# 05-MCU_02.net
KiCad netlist of a schematic drawn in Altium Designer
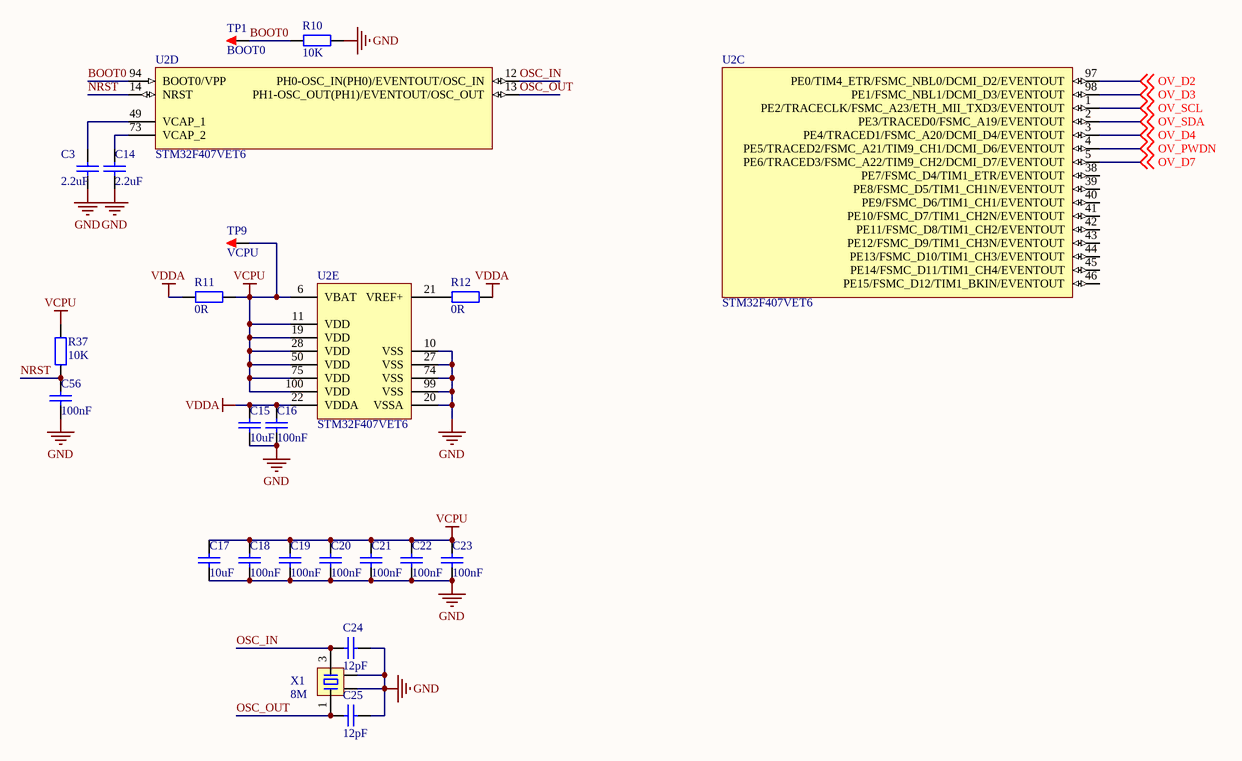
[diagram p0: 05-MCU_02.SchDoc]

(export (version "E")
  (design (tool "Eeschema 10.0.6"))
  (components
    (comp (ref "C3")
      (value "2.2uF")
      (footprint "C0603_M")
      (description "贴片电容/MLCC电容")
      (libsource (lib "0.1 - 电阻-电容-电感-保险丝-晶振-晶体-磁珠-电位器-法拉电容-馈通电容") (part "C"))
    )
    (comp (ref "C14")
      (value "2.2uF")
      (footprint "C0603_M")
      (description "贴片电容/MLCC电容")
      (libsource (lib "0.1 - 电阻-电容-电感-保险丝-晶振-晶体-磁珠-电位器-法拉电容-馈通电容") (part "C"))
    )
    (comp (ref "C15")
      (value "10uF")
      (footprint "C0603_M")
      (description "贴片电容/MLCC电容")
      (libsource (lib "0.1 - 电阻-电容-电感-保险丝-晶振-晶体-磁珠-电位器-法拉电容-馈通电容") (part "C"))
    )
    (comp (ref "C16")
      (value "100nF")
      (footprint "C0603_M")
      (description "贴片电容/MLCC电容")
      (libsource (lib "0.1 - 电阻-电容-电感-保险丝-晶振-晶体-磁珠-电位器-法拉电容-馈通电容") (part "C"))
    )
    (comp (ref "C17")
      (value "10uF")
      (footprint "C0603_M")
      (description "贴片电容/MLCC电容")
      (libsource (lib "0.1 - 电阻-电容-电感-保险丝-晶振-晶体-磁珠-电位器-法拉电容-馈通电容") (part "C"))
    )
    (comp (ref "C18")
      (value "100nF")
      (footprint "C0603_M")
      (description "贴片电容/MLCC电容")
      (libsource (lib "0.1 - 电阻-电容-电感-保险丝-晶振-晶体-磁珠-电位器-法拉电容-馈通电容") (part "C"))
    )
    (comp (ref "C19")
      (value "100nF")
      (footprint "C0603_M")
      (description "贴片电容/MLCC电容")
      (libsource (lib "0.1 - 电阻-电容-电感-保险丝-晶振-晶体-磁珠-电位器-法拉电容-馈通电容") (part "C"))
    )
    (comp (ref "C20")
      (value "100nF")
      (footprint "C0603_M")
      (description "贴片电容/MLCC电容")
      (libsource (lib "0.1 - 电阻-电容-电感-保险丝-晶振-晶体-磁珠-电位器-法拉电容-馈通电容") (part "C"))
    )
    (comp (ref "C21")
      (value "100nF")
      (footprint "C0603_M")
      (description "贴片电容/MLCC电容")
      (libsource (lib "0.1 - 电阻-电容-电感-保险丝-晶振-晶体-磁珠-电位器-法拉电容-馈通电容") (part "C"))
    )
    (comp (ref "C22")
      (value "100nF")
      (footprint "C0603_M")
      (description "贴片电容/MLCC电容")
      (libsource (lib "0.1 - 电阻-电容-电感-保险丝-晶振-晶体-磁珠-电位器-法拉电容-馈通电容") (part "C"))
    )
    (comp (ref "C23")
      (value "100nF")
      (footprint "C0603_M")
      (description "贴片电容/MLCC电容")
      (libsource (lib "0.1 - 电阻-电容-电感-保险丝-晶振-晶体-磁珠-电位器-法拉电容-馈通电容") (part "C"))
    )
    (comp (ref "C24")
      (value "12pF")
      (footprint "C0603_M")
      (description "贴片电容/MLCC电容")
      (libsource (lib "0.1 - 电阻-电容-电感-保险丝-晶振-晶体-磁珠-电位器-法拉电容-馈通电容") (part "C"))
    )
    (comp (ref "C25")
      (value "12pF")
      (footprint "C0603_M")
      (description "贴片电容/MLCC电容")
      (libsource (lib "0.1 - 电阻-电容-电感-保险丝-晶振-晶体-磁珠-电位器-法拉电容-馈通电容") (part "C"))
    )
    (comp (ref "C56")
      (value "100nF")
      (footprint "C0603_M")
      (description "贴片电容/MLCC电容")
      (libsource (lib "0.1 - 电阻-电容-电感-保险丝-晶振-晶体-磁珠-电位器-法拉电容-馈通电容") (part "C"))
    )
    (comp (ref "R10")
      (value "10K")
      (footprint "R0603_M")
      (description "贴片电阻")
      (libsource (lib "0.1 - 电阻-电容-电感-保险丝-晶振-晶体-磁珠-电位器-法拉电容-馈通电容") (part "R"))
    )
    (comp (ref "R11")
      (value "0R")
      (footprint "R0603_M")
      (description "贴片电阻")
      (libsource (lib "0.1 - 电阻-电容-电感-保险丝-晶振-晶体-磁珠-电位器-法拉电容-馈通电容") (part "R"))
    )
    (comp (ref "R12")
      (value "0R")
      (footprint "R0603_M")
      (description "贴片电阻")
      (libsource (lib "0.1 - 电阻-电容-电感-保险丝-晶振-晶体-磁珠-电位器-法拉电容-馈通电容") (part "R"))
    )
    (comp (ref "R37")
      (value "10K")
      (footprint "R0603_M")
      (description "贴片电阻")
      (libsource (lib "0.1 - 电阻-电容-电感-保险丝-晶振-晶体-磁珠-电位器-法拉电容-馈通电容") (part "R"))
    )
    (comp (ref "TP1")
      (value "BOOT0")
      (footprint "TEST 1.6")
      (description "测试点")
      (libsource (lib "0.5 - 按键_开关_蜂鸣器_电池_测试点_Mark点_铜柱") (part "TEST"))
    )
    (comp (ref "TP9")
      (value "VCPU")
      (footprint "TEST 1.6")
      (description "测试点")
      (libsource (lib "0.5 - 按键_开关_蜂鸣器_电池_测试点_Mark点_铜柱") (part "TEST"))
    )
    (comp (ref "U2")
      (value "STM32F407VET6")
      (footprint "LQFP100_V")
      (libsource (lib "STM32 F4") (part "STM32F407VET6"))
    )
    (comp (ref "X1")
      (value "8M")
      (footprint "XTAL-3225-4P")
      (description "4脚无源晶振(谐振器）")
      (libsource (lib "0.1 - 电阻-电容-电感-保险丝-晶振-晶体-磁珠-电位器-法拉电容-馈通电容") (part "XTAL-4P"))
    )
  )
  (nets
    (net (code "1") (name "/BOOT0") (class "Default")
      (node (ref "R10") (pin "2") (pinfunction "2_2") (pintype "passive"))
      (node (ref "TP1") (pin "1") (pinfunction "1_1") (pintype "passive"))
      (node (ref "U2") (pin "94") (pinfunction "BOOT0/VPP_94") (pintype "input"))
    )
    (net (code "2") (name "/NRST") (class "Default")
      (node (ref "C56") (pin "1") (pinfunction "1_1") (pintype "passive"))
      (node (ref "R37") (pin "1") (pinfunction "1_1") (pintype "passive"))
      (node (ref "U2") (pin "14") (pinfunction "NRST_14") (pintype "bidirectional"))
    )
    (net (code "3") (name "/OSC_IN") (class "Default")
      (node (ref "C24") (pin "1") (pinfunction "1_1") (pintype "passive"))
      (node (ref "U2") (pin "12") (pinfunction "PH0-OSC_IN(PH0)/EVENTOUT/OSC_IN_12") (pintype "bidirectional"))
      (node (ref "X1") (pin "3") (pinfunction "3_3") (pintype "passive"))
    )
    (net (code "4") (name "/OSC_OUT") (class "Default")
      (node (ref "C25") (pin "1") (pinfunction "1_1") (pintype "passive"))
      (node (ref "U2") (pin "13") (pinfunction "PH1-OSC_OUT(PH1)/EVENTOUT/OSC_OUT_13") (pintype "bidirectional"))
      (node (ref "X1") (pin "1") (pinfunction "1_1") (pintype "passive"))
    )
    (net (code "5") (name "GND") (class "Default")
      (node (ref "C14") (pin "2") (pinfunction "2_2") (pintype "passive"))
      (node (ref "C15") (pin "2") (pinfunction "2_2") (pintype "passive"))
      (node (ref "C16") (pin "2") (pinfunction "2_2") (pintype "passive"))
      (node (ref "C17") (pin "2") (pinfunction "2_2") (pintype "passive"))
      (node (ref "C18") (pin "2") (pinfunction "2_2") (pintype "passive"))
      (node (ref "C19") (pin "2") (pinfunction "2_2") (pintype "passive"))
      (node (ref "C20") (pin "2") (pinfunction "2_2") (pintype "passive"))
      (node (ref "C21") (pin "2") (pinfunction "2_2") (pintype "passive"))
      (node (ref "C22") (pin "2") (pinfunction "2_2") (pintype "passive"))
      (node (ref "C23") (pin "2") (pinfunction "2_2") (pintype "passive"))
      (node (ref "C24") (pin "2") (pinfunction "2_2") (pintype "passive"))
      (node (ref "C25") (pin "2") (pinfunction "2_2") (pintype "passive"))
      (node (ref "C3") (pin "2") (pinfunction "2_2") (pintype "passive"))
      (node (ref "C56") (pin "2") (pinfunction "2_2") (pintype "passive"))
      (node (ref "R10") (pin "1") (pinfunction "1_1") (pintype "passive"))
      (node (ref "U2") (pin "10") (pinfunction "VSS_10") (pintype "power_in"))
      (node (ref "U2") (pin "20") (pinfunction "VSSA_20") (pintype "power_in"))
      (node (ref "U2") (pin "27") (pinfunction "VSS_27") (pintype "power_in"))
      (node (ref "U2") (pin "74") (pinfunction "VSS_74") (pintype "power_in"))
      (node (ref "U2") (pin "99") (pinfunction "VSS_99") (pintype "power_in"))
      (node (ref "X1") (pin "2") (pinfunction "2_2") (pintype "passive"))
      (node (ref "X1") (pin "4") (pinfunction "4_4") (pintype "passive"))
    )
    (net (code "6") (name "Net-(U2D-VCAP_1)") (class "Default")
      (node (ref "C3") (pin "1") (pinfunction "1_1") (pintype "passive"))
      (node (ref "U2") (pin "49") (pinfunction "VCAP_1_49") (pintype "power_in"))
    )
    (net (code "7") (name "Net-(U2D-VCAP_2)") (class "Default")
      (node (ref "C14") (pin "1") (pinfunction "1_1") (pintype "passive"))
      (node (ref "U2") (pin "73") (pinfunction "VCAP_2_73") (pintype "power_in"))
    )
    (net (code "8") (name "Net-(U2E-VREF+)") (class "Default")
      (node (ref "R12") (pin "2") (pinfunction "2_2") (pintype "passive"))
      (node (ref "U2") (pin "21") (pinfunction "VREF+_21") (pintype "power_in"))
    )
    (net (code "9") (name "OV_D2") (class "Default")
      (node (ref "U2") (pin "97") (pinfunction "PE0/TIM4_ETR/FSMC_NBL0/DCMI_D2/EVENTOUT_97") (pintype "bidirectional"))
    )
    (net (code "10") (name "OV_D3") (class "Default")
      (node (ref "U2") (pin "98") (pinfunction "PE1/FSMC_NBL1/DCMI_D3/EVENTOUT_98") (pintype "bidirectional"))
    )
    (net (code "11") (name "OV_D4") (class "Default")
      (node (ref "U2") (pin "3") (pinfunction "PE4/TRACED1/FSMC_A20/DCMI_D4/EVENTOUT_3") (pintype "bidirectional"))
    )
    (net (code "12") (name "OV_D7") (class "Default")
      (node (ref "U2") (pin "5") (pinfunction "PE6/TRACED3/FSMC_A22/TIM9_CH2/DCMI_D7/EVENTOUT_5") (pintype "bidirectional"))
    )
    (net (code "13") (name "OV_PWDN") (class "Default")
      (node (ref "U2") (pin "4") (pinfunction "PE5/TRACED2/FSMC_A21/TIM9_CH1/DCMI_D6/EVENTOUT_4") (pintype "bidirectional"))
    )
    (net (code "14") (name "OV_SCL") (class "Default")
      (node (ref "U2") (pin "1") (pinfunction "PE2/TRACECLK/FSMC_A23/ETH_MII_TXD3/EVENTOUT_1") (pintype "bidirectional"))
    )
    (net (code "15") (name "OV_SDA") (class "Default")
      (node (ref "U2") (pin "2") (pinfunction "PE3/TRACED0/FSMC_A19/EVENTOUT_2") (pintype "bidirectional"))
    )
    (net (code "16") (name "VCPU") (class "Default")
      (node (ref "C17") (pin "1") (pinfunction "1_1") (pintype "passive"))
      (node (ref "C18") (pin "1") (pinfunction "1_1") (pintype "passive"))
      (node (ref "C19") (pin "1") (pinfunction "1_1") (pintype "passive"))
      (node (ref "C20") (pin "1") (pinfunction "1_1") (pintype "passive"))
      (node (ref "C21") (pin "1") (pinfunction "1_1") (pintype "passive"))
      (node (ref "C22") (pin "1") (pinfunction "1_1") (pintype "passive"))
      (node (ref "C23") (pin "1") (pinfunction "1_1") (pintype "passive"))
      (node (ref "R11") (pin "1") (pinfunction "1_1") (pintype "passive"))
      (node (ref "R37") (pin "2") (pinfunction "2_2") (pintype "passive"))
      (node (ref "TP9") (pin "1") (pinfunction "1_1") (pintype "passive"))
      (node (ref "U2") (pin "100") (pinfunction "VDD_100") (pintype "power_in"))
      (node (ref "U2") (pin "11") (pinfunction "VDD_11") (pintype "power_in"))
      (node (ref "U2") (pin "19") (pinfunction "VDD_19") (pintype "power_in"))
      (node (ref "U2") (pin "28") (pinfunction "VDD_28") (pintype "power_in"))
      (node (ref "U2") (pin "50") (pinfunction "VDD_50") (pintype "power_in"))
      (node (ref "U2") (pin "6") (pinfunction "VBAT_6") (pintype "power_in"))
      (node (ref "U2") (pin "75") (pinfunction "VDD_75") (pintype "power_in"))
    )
    (net (code "17") (name "VDDA") (class "Default")
      (node (ref "C15") (pin "1") (pinfunction "1_1") (pintype "passive"))
      (node (ref "C16") (pin "1") (pinfunction "1_1") (pintype "passive"))
      (node (ref "R11") (pin "2") (pinfunction "2_2") (pintype "passive"))
      (node (ref "R12") (pin "1") (pinfunction "1_1") (pintype "passive"))
      (node (ref "U2") (pin "22") (pinfunction "VDDA_22") (pintype "power_in"))
    )
    (net (code "18") (name "unconnected-(U2C-PE7{slash}FSMC_D4{slash}TIM1_ETR{slash}EVENTOUT-Pad38)") (class "Default")
      (node (ref "U2") (pin "38") (pinfunction "PE7/FSMC_D4/TIM1_ETR/EVENTOUT_38") (pintype "bidirectional"))
    )
    (net (code "19") (name "unconnected-(U2C-PE8{slash}FSMC_D5{slash}TIM1_CH1N{slash}EVENTOUT-Pad39)") (class "Default")
      (node (ref "U2") (pin "39") (pinfunction "PE8/FSMC_D5/TIM1_CH1N/EVENTOUT_39") (pintype "bidirectional"))
    )
    (net (code "20") (name "unconnected-(U2C-PE9{slash}FSMC_D6{slash}TIM1_CH1{slash}EVENTOUT-Pad40)") (class "Default")
      (node (ref "U2") (pin "40") (pinfunction "PE9/FSMC_D6/TIM1_CH1/EVENTOUT_40") (pintype "bidirectional"))
    )
    (net (code "21") (name "unconnected-(U2C-PE10{slash}FSMC_D7{slash}TIM1_CH2N{slash}EVENTOUT-Pad41)") (class "Default")
      (node (ref "U2") (pin "41") (pinfunction "PE10/FSMC_D7/TIM1_CH2N/EVENTOUT_41") (pintype "bidirectional"))
    )
    (net (code "22") (name "unconnected-(U2C-PE11{slash}FSMC_D8{slash}TIM1_CH2{slash}EVENTOUT-Pad42)") (class "Default")
      (node (ref "U2") (pin "42") (pinfunction "PE11/FSMC_D8/TIM1_CH2/EVENTOUT_42") (pintype "bidirectional"))
    )
    (net (code "23") (name "unconnected-(U2C-PE12{slash}FSMC_D9{slash}TIM1_CH3N{slash}EVENTOUT-Pad43)") (class "Default")
      (node (ref "U2") (pin "43") (pinfunction "PE12/FSMC_D9/TIM1_CH3N/EVENTOUT_43") (pintype "bidirectional"))
    )
    (net (code "24") (name "unconnected-(U2C-PE13{slash}FSMC_D10{slash}TIM1_CH3{slash}EVENTOUT-Pad44)") (class "Default")
      (node (ref "U2") (pin "44") (pinfunction "PE13/FSMC_D10/TIM1_CH3/EVENTOUT_44") (pintype "bidirectional"))
    )
    (net (code "25") (name "unconnected-(U2C-PE14{slash}FSMC_D11{slash}TIM1_CH4{slash}EVENTOUT-Pad45)") (class "Default")
      (node (ref "U2") (pin "45") (pinfunction "PE14/FSMC_D11/TIM1_CH4/EVENTOUT_45") (pintype "bidirectional"))
    )
    (net (code "26") (name "unconnected-(U2C-PE15{slash}FSMC_D12{slash}TIM1_BKIN{slash}EVENTOUT-Pad46)") (class "Default")
      (node (ref "U2") (pin "46") (pinfunction "PE15/FSMC_D12/TIM1_BKIN/EVENTOUT_46") (pintype "bidirectional"))
    )
  )
)
